# CAN-BUS-UART_v2.net
KiCad netlist of a schematic drawn in EAGLE
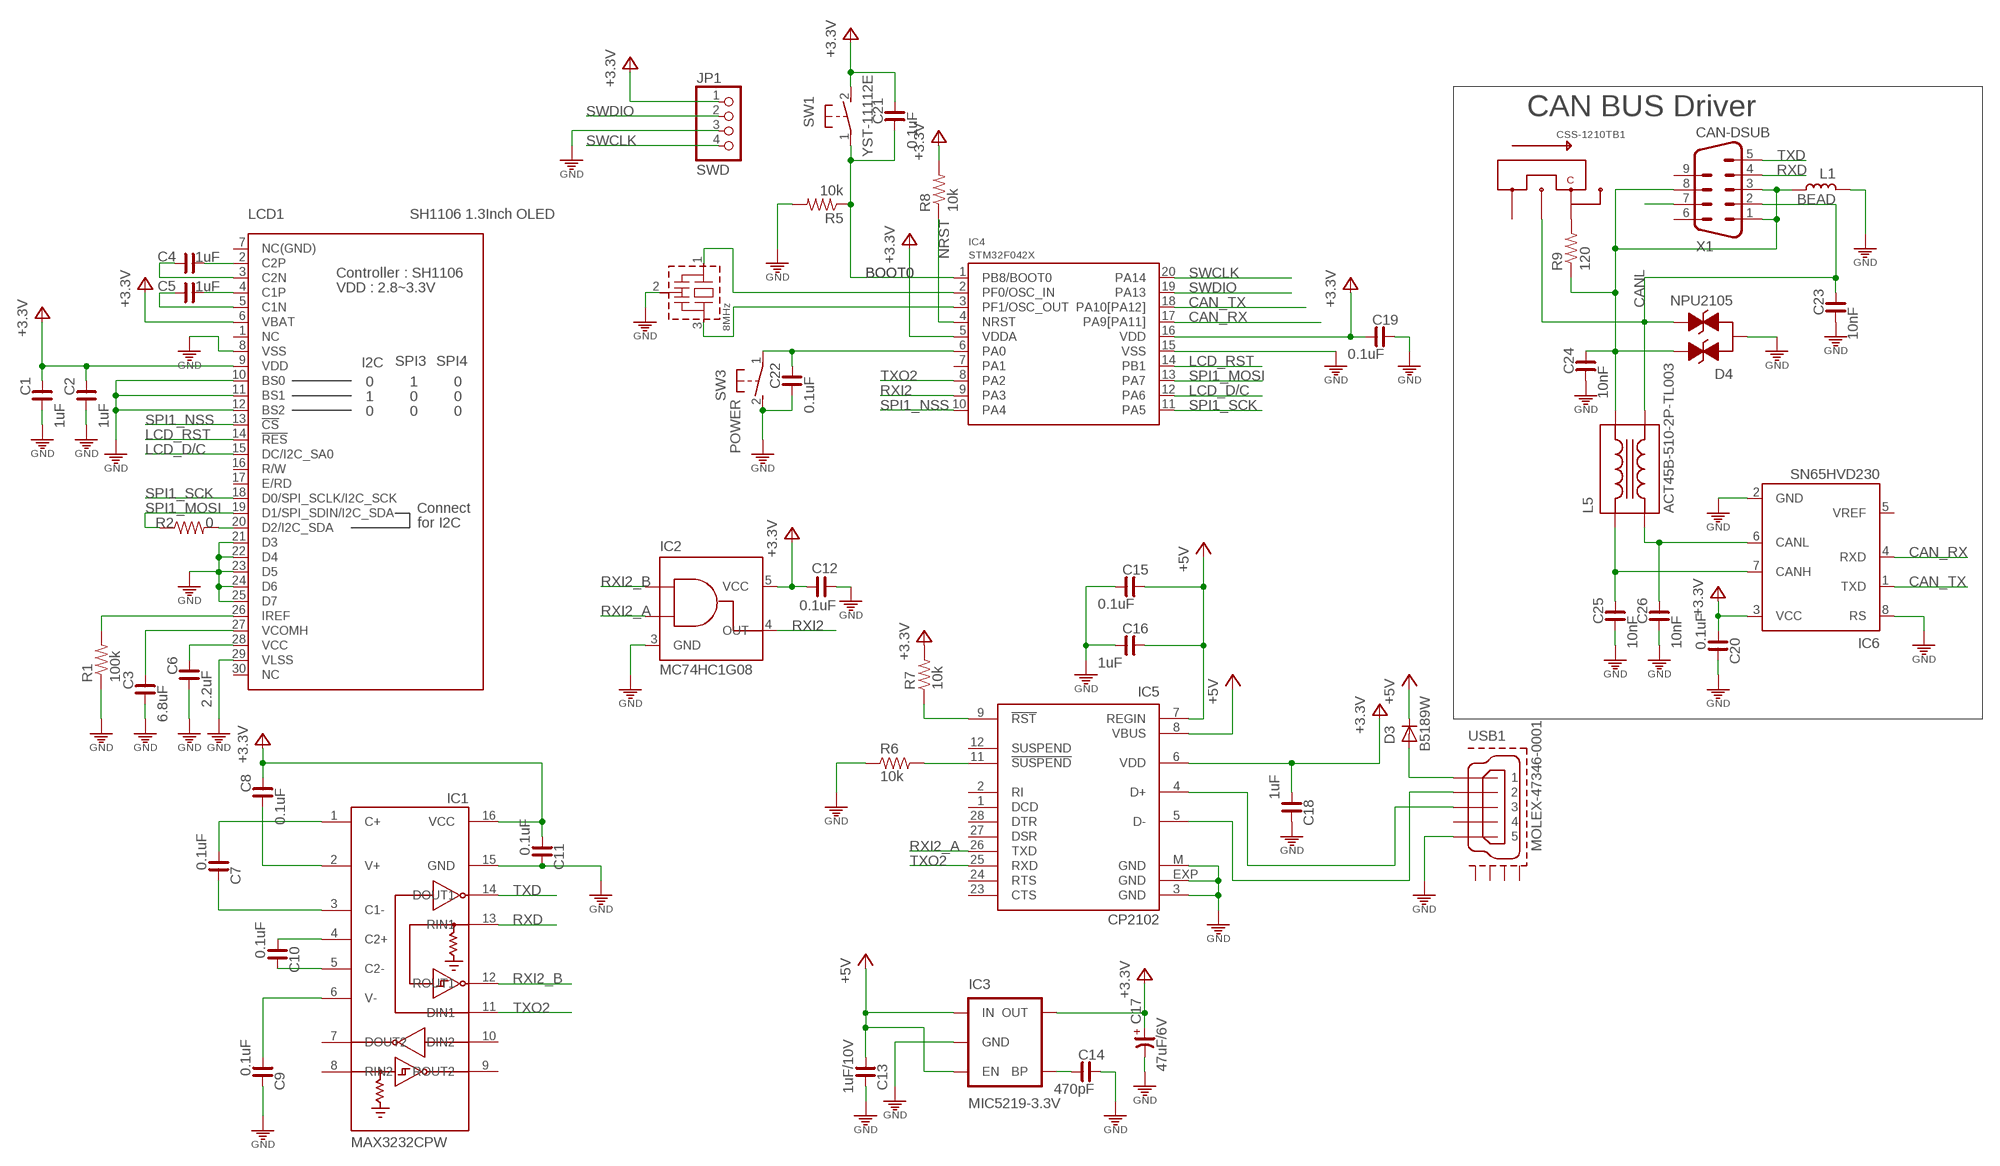
[diagram p0: schematic, sheet 1]

(export (version "E")
  (design (tool "Eeschema 10.0.6"))
  (components
    (comp (ref "C1")
      (value "1uF")
      (footprint "eagle-import:C0603")
      (libsource (lib "eagle-import") (part "C_0603"))
    )
    (comp (ref "C2")
      (value "1uF")
      (footprint "eagle-import:C0603")
      (libsource (lib "eagle-import") (part "C_0603"))
    )
    (comp (ref "C3")
      (value "6.8uF")
      (footprint "eagle-import:C0805")
      (libsource (lib "eagle-import") (part "C_0805"))
    )
    (comp (ref "C4")
      (value "1uF")
      (footprint "eagle-import:C0603")
      (libsource (lib "eagle-import") (part "C_0603"))
    )
    (comp (ref "C5")
      (value "1uF")
      (footprint "eagle-import:C0603")
      (libsource (lib "eagle-import") (part "C_0603"))
    )
    (comp (ref "C6")
      (value "2.2uF")
      (footprint "eagle-import:C0805")
      (libsource (lib "eagle-import") (part "C_0805"))
    )
    (comp (ref "C7")
      (value "0.1uF")
      (footprint "eagle-import:C0603")
      (libsource (lib "eagle-import") (part "C_0603"))
    )
    (comp (ref "C8")
      (value "0.1uF")
      (footprint "eagle-import:C0603")
      (libsource (lib "eagle-import") (part "C_0603"))
    )
    (comp (ref "C9")
      (value "0.1uF")
      (footprint "eagle-import:C0603")
      (libsource (lib "eagle-import") (part "C_0603"))
    )
    (comp (ref "C10")
      (value "0.1uF")
      (footprint "eagle-import:C0603")
      (libsource (lib "eagle-import") (part "C_0603"))
    )
    (comp (ref "C11")
      (value "0.1uF")
      (footprint "eagle-import:C0603")
      (libsource (lib "eagle-import") (part "C_0603"))
    )
    (comp (ref "C12")
      (value "0.1uF")
      (footprint "eagle-import:C0603")
      (libsource (lib "eagle-import") (part "C_0603"))
    )
    (comp (ref "C13")
      (value "1uF/10V")
      (footprint "eagle-import:C0603")
      (libsource (lib "eagle-import") (part "C_0603"))
    )
    (comp (ref "C14")
      (value "470pF")
      (footprint "eagle-import:C0603")
      (libsource (lib "eagle-import") (part "C_0603"))
    )
    (comp (ref "C15")
      (value "0.1uF")
      (footprint "eagle-import:C0603")
      (libsource (lib "eagle-import") (part "C_0603"))
    )
    (comp (ref "C16")
      (value "1uF")
      (footprint "eagle-import:C0603")
      (libsource (lib "eagle-import") (part "C_0603"))
    )
    (comp (ref "C17")
      (value "47uF/6V")
      (footprint "eagle-import:C3528-21_T")
      (libsource (lib "eagle-import") (part "CP_3528-21"))
    )
    (comp (ref "C18")
      (value "1uF")
      (footprint "eagle-import:C0603")
      (libsource (lib "eagle-import") (part "C_0603"))
    )
    (comp (ref "C19")
      (value "0.1uF")
      (footprint "eagle-import:C0603")
      (libsource (lib "eagle-import") (part "C_0603"))
    )
    (comp (ref "C20")
      (value "0.1uF")
      (footprint "eagle-import:C0603")
      (libsource (lib "eagle-import") (part "C_0603"))
    )
    (comp (ref "C21")
      (value "0.1uF")
      (footprint "eagle-import:C0603")
      (libsource (lib "eagle-import") (part "C_0603"))
    )
    (comp (ref "C22")
      (value "0.1uF")
      (footprint "eagle-import:C0603")
      (libsource (lib "eagle-import") (part "C_0603"))
    )
    (comp (ref "C23")
      (value "10nF")
      (footprint "eagle-import:C0603")
      (libsource (lib "eagle-import") (part "C_0603"))
    )
    (comp (ref "C24")
      (value "10nF")
      (footprint "eagle-import:C0603")
      (libsource (lib "eagle-import") (part "C_0603"))
    )
    (comp (ref "C25")
      (value "10nF")
      (footprint "eagle-import:C0603")
      (libsource (lib "eagle-import") (part "C_0603"))
    )
    (comp (ref "C26")
      (value "10nF")
      (footprint "eagle-import:C0603")
      (libsource (lib "eagle-import") (part "C_0603"))
    )
    (comp (ref "D3")
      (value "B5189W")
      (footprint "eagle-import:SOD323")
      (libsource (lib "eagle-import") (part "B5189WN"))
    )
    (comp (ref "D4")
      (value "NPU2105")
      (footprint "eagle-import:SOT23")
      (libsource (lib "eagle-import") (part "NPU2105"))
    )
    (comp (ref "IC1")
      (value "MAX3232CPW")
      (footprint "eagle-import:PW_R-PDSO-G16")
      (libsource (lib "eagle-import") (part "MAX3232MAX232CPW"))
    )
    (comp (ref "IC2")
      (value "MC74HC1G08")
      (footprint "eagle-import:SOT23-5L_MC74HC1G08")
      (libsource (lib "eagle-import") (part "AND_GATE_2INMC74HC1G08"))
    )
    (comp (ref "IC3")
      (value "MIC5219-3.3V")
      (footprint "eagle-import:SOT23-5")
      (libsource (lib "eagle-import") (part "V_REG_LDOSMD"))
    )
    (comp (ref "IC4")
      (value "STM32F042X")
      (footprint "eagle-import:TSSOP20")
      (libsource (lib "eagle-import") (part "STM32F042X"))
    )
    (comp (ref "IC5")
      (value "CP2102")
      (footprint "eagle-import:MLP28")
      (fields (field (name "MF") "FARNELL") (field (name "MPN") "CP2102-GM"))
      (libsource (lib "eagle-import") (part "CP2102"))
    )
    (comp (ref "IC6")
      (value "SN65HVD230")
      (footprint "eagle-import:SO8")
      (libsource (lib "eagle-import") (part "PCA82C250T"))
    )
    (comp (ref "JP1")
      (value "SWD")
      (footprint "eagle-import:1X04M")
      (libsource (lib "eagle-import") (part "PINHD-1X4M"))
    )
    (comp (ref "L1")
      (value "BEAD")
      (footprint "eagle-import:L0805")
      (libsource (lib "eagle-import") (part "L_0805"))
    )
    (comp (ref "L5")
      (value "ACT45B-510-2P-TL003")
      (footprint "eagle-import:ACT45B")
      (libsource (lib "eagle-import") (part "CHOKE_COIL"))
    )
    (comp (ref "LCD1")
      (value "SH1106 1.3Inch OLED")
      (footprint "eagle-import:SH1106_1.3OLED_BUTTOM")
      (libsource (lib "eagle-import") (part "SH1106_1.3_OLEDBUTTOM"))
    )
    (comp (ref "Q1")
      (value "8MHz")
      (footprint "eagle-import:CSTLA_X")
      (libsource (lib "eagle-import") (part "X-TAL-SMALLCSTCE16M00V53"))
    )
    (comp (ref "R1")
      (value "100k")
      (footprint "eagle-import:R0603@1")
      (libsource (lib "eagle-import") (part "R-US_R1608"))
    )
    (comp (ref "R2")
      (value "0")
      (footprint "eagle-import:R0603@1")
      (libsource (lib "eagle-import") (part "R-US_R1608"))
    )
    (comp (ref "R5")
      (value "10k")
      (footprint "eagle-import:R0603@1")
      (libsource (lib "eagle-import") (part "R-US_R1608"))
    )
    (comp (ref "R6")
      (value "10k")
      (footprint "eagle-import:R0603")
      (libsource (lib "eagle-import") (part "R_0603"))
    )
    (comp (ref "R7")
      (value "10k")
      (footprint "eagle-import:R0603")
      (libsource (lib "eagle-import") (part "R_0603"))
    )
    (comp (ref "R8")
      (value "10k")
      (footprint "eagle-import:R0603@1")
      (libsource (lib "eagle-import") (part "R-US_R1608"))
    )
    (comp (ref "R9")
      (value "120")
      (footprint "eagle-import:R0603@1")
      (libsource (lib "eagle-import") (part "R-US_R1608"))
    )
    (comp (ref "SW1")
      (value "YST-11112E")
      (footprint "eagle-import:YST-1112E")
      (libsource (lib "eagle-import") (part "YST-11112E"))
    )
    (comp (ref "SW2")
      (value "CSS-1210TB1")
      (footprint "eagle-import:CSS-1210TB")
      (libsource (lib "eagle-import") (part "CSS-1210TB1"))
    )
    (comp (ref "SW3")
      (value "POWER")
      (footprint "eagle-import:KLT-1105VE")
      (libsource (lib "eagle-import") (part "KLT-1105VE"))
    )
    (comp (ref "USB1")
      (value "MOLEX-47346-0001")
      (footprint "eagle-import:MOLEX-47364-0001")
      (libsource (lib "eagle-import") (part "MOLEX-47346-0001"))
    )
    (comp (ref "X1")
      (value "CAN-DSUB")
      (footprint "eagle-import:M09H-1")
      (libsource (lib "eagle-import") (part "M09KR"))
    )
  )
  (nets
    (net (code "1") (name "+3V3") (class "Default")
      (node (ref "C1") (pin "1") (pinfunction "1_1") (pintype "passive"))
      (node (ref "C11") (pin "2") (pinfunction "2_2") (pintype "passive"))
      (node (ref "C12") (pin "2") (pinfunction "2_2") (pintype "passive"))
      (node (ref "C17") (pin "+") (pinfunction "+_+") (pintype "passive"))
      (node (ref "C18") (pin "2") (pinfunction "2_2") (pintype "passive"))
      (node (ref "C19") (pin "2") (pinfunction "2_2") (pintype "passive"))
      (node (ref "C2") (pin "1") (pinfunction "1_1") (pintype "passive"))
      (node (ref "C20") (pin "2") (pinfunction "2_2") (pintype "passive"))
      (node (ref "C21") (pin "1") (pinfunction "1_1") (pintype "passive"))
      (node (ref "C8") (pin "1") (pinfunction "1_1") (pintype "passive"))
      (node (ref "IC1") (pin "16") (pinfunction "VCC_16") (pintype "power_in"))
      (node (ref "IC2") (pin "5") (pinfunction "VCC_5") (pintype "passive"))
      (node (ref "IC3") (pin "5") (pinfunction "OUT_5") (pintype "passive"))
      (node (ref "IC4") (pin "16") (pinfunction "VDD_16") (pintype "power_in"))
      (node (ref "IC4") (pin "5") (pinfunction "VDDA_5") (pintype "power_in"))
      (node (ref "IC5") (pin "6") (pinfunction "VDD_6") (pintype "power_in"))
      (node (ref "IC6") (pin "3") (pinfunction "VCC_3") (pintype "power_in"))
      (node (ref "JP1") (pin "1") (pinfunction "1_1") (pintype "passive"))
      (node (ref "LCD1") (pin "6") (pinfunction "VBAT_6") (pintype "passive"))
      (node (ref "LCD1") (pin "9") (pinfunction "VDD_9") (pintype "passive"))
      (node (ref "R7") (pin "2") (pinfunction "2_2") (pintype "passive"))
      (node (ref "R8") (pin "2") (pinfunction "2_2") (pintype "passive"))
      (node (ref "SW1") (pin "2") (pinfunction "2_2") (pintype "passive"))
    )
    (net (code "2") (name "+5V") (class "Default")
      (node (ref "C13") (pin "2") (pinfunction "2_2") (pintype "passive"))
      (node (ref "C15") (pin "1") (pinfunction "1_1") (pintype "passive"))
      (node (ref "C16") (pin "1") (pinfunction "1_1") (pintype "passive"))
      (node (ref "D3") (pin "C") (pinfunction "C_C") (pintype "passive"))
      (node (ref "IC3") (pin "1") (pinfunction "IN_1") (pintype "input"))
      (node (ref "IC3") (pin "3") (pinfunction "EN_3") (pintype "input"))
      (node (ref "IC5") (pin "7") (pinfunction "REGIN_7") (pintype "passive"))
      (node (ref "IC5") (pin "8") (pinfunction "VBUS_8") (pintype "input"))
    )
    (net (code "3") (name "/BOOT0") (class "Default")
      (node (ref "C21") (pin "2") (pinfunction "2_2") (pintype "passive"))
      (node (ref "IC4") (pin "1") (pinfunction "PB8/BOOT0_1") (pintype "bidirectional"))
      (node (ref "R5") (pin "1") (pinfunction "1_1") (pintype "passive"))
      (node (ref "SW1") (pin "1") (pinfunction "1_1") (pintype "passive"))
    )
    (net (code "4") (name "/CANL") (class "Default")
      (node (ref "C23") (pin "1") (pinfunction "1_1") (pintype "passive"))
      (node (ref "D4") (pin "S") (pinfunction "PIN2_S") (pintype "passive"))
      (node (ref "L5") (pin "3") (pinfunction "3_3") (pintype "passive"))
      (node (ref "SW2") (pin "2") (pinfunction "2_2") (pintype "bidirectional"))
      (node (ref "X1") (pin "2") (pinfunction "2_2") (pintype "passive"))
    )
    (net (code "5") (name "/CAN_RX") (class "Default")
      (node (ref "IC4") (pin "17") (pinfunction "PA9[PA11]_17") (pintype "bidirectional"))
      (node (ref "IC6") (pin "4") (pinfunction "RXD_4") (pintype "output"))
    )
    (net (code "6") (name "/CAN_TX") (class "Default")
      (node (ref "IC4") (pin "18") (pinfunction "PA10[PA12]_18") (pintype "bidirectional"))
      (node (ref "IC6") (pin "1") (pinfunction "TXD_1") (pintype "input"))
    )
    (net (code "7") (name "/LCD_D{slash}C") (class "Default")
      (node (ref "IC4") (pin "12") (pinfunction "PA6_12") (pintype "bidirectional"))
      (node (ref "LCD1") (pin "15") (pinfunction "DC/I2C_SA0_15") (pintype "passive"))
    )
    (net (code "8") (name "/LCD_RST") (class "Default")
      (node (ref "IC4") (pin "14") (pinfunction "PB1_14") (pintype "bidirectional"))
      (node (ref "LCD1") (pin "14") (pinfunction "~{RES}_14") (pintype "passive"))
    )
    (net (code "9") (name "/NRST") (class "Default")
      (node (ref "IC4") (pin "4") (pinfunction "NRST_4") (pintype "bidirectional"))
      (node (ref "R8") (pin "1") (pinfunction "1_1") (pintype "passive"))
    )
    (net (code "10") (name "/RXD") (class "Default")
      (node (ref "IC1") (pin "13") (pinfunction "RIN1_13") (pintype "input"))
      (node (ref "X1") (pin "4") (pinfunction "4_4") (pintype "passive"))
    )
    (net (code "11") (name "/RXI2") (class "Default")
      (node (ref "IC2") (pin "4") (pinfunction "OUT_4") (pintype "output"))
      (node (ref "IC4") (pin "9") (pinfunction "PA3_9") (pintype "bidirectional"))
    )
    (net (code "12") (name "/RXI2_A") (class "Default")
      (node (ref "IC2") (pin "2") (pinfunction "INA_2") (pintype "input"))
      (node (ref "IC5") (pin "26") (pinfunction "TXD_26") (pintype "output"))
    )
    (net (code "13") (name "/RXI2_B") (class "Default")
      (node (ref "IC1") (pin "12") (pinfunction "ROUT1_12") (pintype "input"))
      (node (ref "IC2") (pin "1") (pinfunction "INB_1") (pintype "input"))
    )
    (net (code "14") (name "/SPI1_MOSI") (class "Default")
      (node (ref "IC4") (pin "13") (pinfunction "PA7_13") (pintype "bidirectional"))
      (node (ref "LCD1") (pin "19") (pinfunction "D1/SPI_SDIN/I2C_SDA_19") (pintype "passive"))
      (node (ref "R2") (pin "1") (pinfunction "1_1") (pintype "passive"))
    )
    (net (code "15") (name "/SPI1_NSS") (class "Default")
      (node (ref "IC4") (pin "10") (pinfunction "PA4_10") (pintype "bidirectional"))
      (node (ref "LCD1") (pin "13") (pinfunction "~{CS}_13") (pintype "passive"))
    )
    (net (code "16") (name "/SPI1_SCK") (class "Default")
      (node (ref "IC4") (pin "11") (pinfunction "PA5_11") (pintype "bidirectional"))
      (node (ref "LCD1") (pin "18") (pinfunction "D0/SPI_SCLK/I2C_SCK_18") (pintype "passive"))
    )
    (net (code "17") (name "/SWCLK") (class "Default")
      (node (ref "IC4") (pin "20") (pinfunction "PA14_20") (pintype "bidirectional"))
      (node (ref "JP1") (pin "4") (pinfunction "4_4") (pintype "passive"))
    )
    (net (code "18") (name "/SWDIO") (class "Default")
      (node (ref "IC4") (pin "19") (pinfunction "PA13_19") (pintype "bidirectional"))
      (node (ref "JP1") (pin "2") (pinfunction "2_2") (pintype "passive"))
    )
    (net (code "19") (name "/TXD") (class "Default")
      (node (ref "IC1") (pin "14") (pinfunction "DOUT1_14") (pintype "output"))
      (node (ref "X1") (pin "5") (pinfunction "5_5") (pintype "passive"))
    )
    (net (code "20") (name "/TXO2") (class "Default")
      (node (ref "IC1") (pin "11") (pinfunction "DIN1_11") (pintype "input"))
      (node (ref "IC4") (pin "8") (pinfunction "PA2_8") (pintype "bidirectional"))
      (node (ref "IC5") (pin "25") (pinfunction "RXD_25") (pintype "input"))
    )
    (net (code "21") (name "GND") (class "Default")
      (node (ref "C1") (pin "2") (pinfunction "2_2") (pintype "passive"))
      (node (ref "C11") (pin "1") (pinfunction "1_1") (pintype "passive"))
      (node (ref "C12") (pin "1") (pinfunction "1_1") (pintype "passive"))
      (node (ref "C13") (pin "1") (pinfunction "1_1") (pintype "passive"))
      (node (ref "C14") (pin "1") (pinfunction "1_1") (pintype "passive"))
      (node (ref "C15") (pin "2") (pinfunction "2_2") (pintype "passive"))
      (node (ref "C16") (pin "2") (pinfunction "2_2") (pintype "passive"))
      (node (ref "C17") (pin "-") (pinfunction "-_-") (pintype "passive"))
      (node (ref "C18") (pin "1") (pinfunction "1_1") (pintype "passive"))
      (node (ref "C19") (pin "1") (pinfunction "1_1") (pintype "passive"))
      (node (ref "C2") (pin "2") (pinfunction "2_2") (pintype "passive"))
      (node (ref "C20") (pin "1") (pinfunction "1_1") (pintype "passive"))
      (node (ref "C22") (pin "2") (pinfunction "2_2") (pintype "passive"))
      (node (ref "C23") (pin "2") (pinfunction "2_2") (pintype "passive"))
      (node (ref "C24") (pin "2") (pinfunction "2_2") (pintype "passive"))
      (node (ref "C25") (pin "2") (pinfunction "2_2") (pintype "passive"))
      (node (ref "C26") (pin "2") (pinfunction "2_2") (pintype "passive"))
      (node (ref "C3") (pin "2") (pinfunction "2_2") (pintype "passive"))
      (node (ref "C6") (pin "2") (pinfunction "2_2") (pintype "passive"))
      (node (ref "C9") (pin "1") (pinfunction "1_1") (pintype "passive"))
      (node (ref "D4") (pin "D") (pinfunction "PIN3_D") (pintype "passive"))
      (node (ref "IC1") (pin "15") (pinfunction "GND_15") (pintype "power_in"))
      (node (ref "IC2") (pin "3") (pinfunction "GND_3") (pintype "passive"))
      (node (ref "IC3") (pin "2") (pinfunction "GND_2") (pintype "input"))
      (node (ref "IC4") (pin "15") (pinfunction "VSS_15") (pintype "power_in"))
      (node (ref "IC5") (pin "3") (pinfunction "GND_3") (pintype "power_in"))
      (node (ref "IC5") (pin "EXP") (pinfunction "GND_EXP") (pintype "power_in"))
      (node (ref "IC5") (pin "M") (pinfunction "GND_M") (pintype "power_in"))
      (node (ref "IC6") (pin "2") (pinfunction "GND_2") (pintype "power_in"))
      (node (ref "IC6") (pin "8") (pinfunction "RS_8") (pintype "input"))
      (node (ref "JP1") (pin "3") (pinfunction "3_3") (pintype "passive"))
      (node (ref "L1") (pin "2") (pinfunction "2_2") (pintype "passive"))
      (node (ref "LCD1") (pin "10") (pinfunction "BS0_10") (pintype "passive"))
      (node (ref "LCD1") (pin "11") (pinfunction "BS1_11") (pintype "passive"))
      (node (ref "LCD1") (pin "12") (pinfunction "BS2_12") (pintype "passive"))
      (node (ref "LCD1") (pin "21") (pinfunction "D3_21") (pintype "passive"))
      (node (ref "LCD1") (pin "22") (pinfunction "D4_22") (pintype "passive"))
      (node (ref "LCD1") (pin "23") (pinfunction "D5_23") (pintype "passive"))
      (node (ref "LCD1") (pin "24") (pinfunction "D6_24") (pintype "passive"))
      (node (ref "LCD1") (pin "25") (pinfunction "D7_25") (pintype "passive"))
      (node (ref "LCD1") (pin "29") (pinfunction "VLSS_29") (pintype "passive"))
      (node (ref "LCD1") (pin "8") (pinfunction "VSS_8") (pintype "passive"))
      (node (ref "Q1") (pin "2") (pinfunction "GND_2") (pintype "power_in"))
      (node (ref "R1") (pin "1") (pinfunction "1_1") (pintype "passive"))
      (node (ref "R5") (pin "2") (pinfunction "2_2") (pintype "passive"))
      (node (ref "R6") (pin "1") (pinfunction "1_1") (pintype "passive"))
      (node (ref "SW3") (pin "2") (pinfunction "2_2") (pintype "passive"))
      (node (ref "USB1") (pin "5") (pinfunction "5_5") (pintype "input"))
    )
    (net (code "22") (name "Net-(D3-PadA)") (class "Default")
      (node (ref "D3") (pin "A") (pinfunction "A_A") (pintype "passive"))
      (node (ref "USB1") (pin "1") (pinfunction "1_1") (pintype "input"))
    )
    (net (code "23") (name "Net-(D4-PIN1)") (class "Default")
      (node (ref "C24") (pin "1") (pinfunction "1_1") (pintype "passive"))
      (node (ref "D4") (pin "G") (pinfunction "PIN1_G") (pintype "passive"))
      (node (ref "L1") (pin "1") (pinfunction "1_1") (pintype "passive"))
      (node (ref "L5") (pin "4") (pinfunction "4_4") (pintype "passive"))
      (node (ref "R9") (pin "1") (pinfunction "1_1") (pintype "passive"))
      (node (ref "X1") (pin "1") (pinfunction "1_1") (pintype "passive"))
      (node (ref "X1") (pin "3") (pinfunction "3_3") (pintype "passive"))
      (node (ref "X1") (pin "8") (pinfunction "8_8") (pintype "passive"))
    )
    (net (code "24") (name "Net-(IC1-C+)") (class "Default")
      (node (ref "C7") (pin "2") (pinfunction "2_2") (pintype "passive"))
      (node (ref "IC1") (pin "1") (pinfunction "C+_1") (pintype "passive"))
    )
    (net (code "25") (name "Net-(IC1-C1-)") (class "Default")
      (node (ref "C7") (pin "1") (pinfunction "1_1") (pintype "passive"))
      (node (ref "IC1") (pin "3") (pinfunction "C1-_3") (pintype "power_in"))
    )
    (net (code "26") (name "Net-(IC1-C2+)") (class "Default")
      (node (ref "C10") (pin "2") (pinfunction "2_2") (pintype "passive"))
      (node (ref "IC1") (pin "4") (pinfunction "C2+_4") (pintype "passive"))
    )
    (net (code "27") (name "Net-(IC1-C2-)") (class "Default")
      (node (ref "C10") (pin "1") (pinfunction "1_1") (pintype "passive"))
      (node (ref "IC1") (pin "5") (pinfunction "C2-_5") (pintype "passive"))
    )
    (net (code "28") (name "Net-(IC1-V+)") (class "Default")
      (node (ref "C8") (pin "2") (pinfunction "2_2") (pintype "passive"))
      (node (ref "IC1") (pin "2") (pinfunction "V+_2") (pintype "passive"))
    )
    (net (code "29") (name "Net-(IC1-V-)") (class "Default")
      (node (ref "C9") (pin "2") (pinfunction "2_2") (pintype "passive"))
      (node (ref "IC1") (pin "6") (pinfunction "V-_6") (pintype "passive"))
    )
    (net (code "30") (name "Net-(IC3-BP)") (class "Default")
      (node (ref "C14") (pin "2") (pinfunction "2_2") (pintype "passive"))
      (node (ref "IC3") (pin "4") (pinfunction "BP_4") (pintype "input"))
    )
    (net (code "31") (name "Net-(IC4-PA0)") (class "Default")
      (node (ref "C22") (pin "1") (pinfunction "1_1") (pintype "passive"))
      (node (ref "IC4") (pin "6") (pinfunction "PA0_6") (pintype "bidirectional"))
      (node (ref "SW3") (pin "1") (pinfunction "1_1") (pintype "passive"))
    )
    (net (code "32") (name "Net-(IC4-PF0{slash}OSC_IN)") (class "Default")
      (node (ref "IC4") (pin "2") (pinfunction "PF0/OSC_IN_2") (pintype "bidirectional"))
      (node (ref "Q1") (pin "1") (pinfunction "IN_1") (pintype "output"))
    )
    (net (code "33") (name "Net-(IC4-PF1{slash}OSC_OUT)") (class "Default")
      (node (ref "IC4") (pin "3") (pinfunction "PF1/OSC_OUT_3") (pintype "bidirectional"))
      (node (ref "Q1") (pin "3") (pinfunction "OUT_3") (pintype "input"))
    )
    (net (code "34") (name "Net-(IC5-D+)") (class "Default")
      (node (ref "IC5") (pin "4") (pinfunction "D+_4") (pintype "bidirectional"))
      (node (ref "USB1") (pin "3") (pinfunction "3_3") (pintype "input"))
    )
    (net (code "35") (name "Net-(IC5-D-)") (class "Default")
      (node (ref "IC5") (pin "5") (pinfunction "D-_5") (pintype "bidirectional"))
      (node (ref "USB1") (pin "2") (pinfunction "2_2") (pintype "input"))
    )
    (net (code "36") (name "Net-(IC5-~{RST})") (class "Default")
      (node (ref "IC5") (pin "9") (pinfunction "~{RST}_9") (pintype "bidirectional"))
      (node (ref "R7") (pin "1") (pinfunction "1_1") (pintype "passive"))
    )
    (net (code "37") (name "Net-(IC5-~{SUSPEND})") (class "Default")
      (node (ref "IC5") (pin "11") (pinfunction "~{SUSPEND}_11") (pintype "output"))
      (node (ref "R6") (pin "2") (pinfunction "2_2") (pintype "passive"))
    )
    (net (code "38") (name "Net-(IC6-CANH)") (class "Default")
      (node (ref "C25") (pin "1") (pinfunction "1_1") (pintype "passive"))
      (node (ref "IC6") (pin "7") (pinfunction "CANH_7") (pintype "bidirectional"))
      (node (ref "L5") (pin "1") (pinfunction "1_1") (pintype "passive"))
    )
    (net (code "39") (name "Net-(IC6-CANL)") (class "Default")
      (node (ref "C26") (pin "1") (pinfunction "1_1") (pintype "passive"))
      (node (ref "IC6") (pin "6") (pinfunction "CANL_6") (pintype "bidirectional"))
      (node (ref "L5") (pin "2") (pinfunction "2_2") (pintype "passive"))
    )
    (net (code "40") (name "Net-(LCD1-C1N)") (class "Default")
      (node (ref "C5") (pin "1") (pinfunction "1_1") (pintype "passive"))
      (node (ref "LCD1") (pin "5") (pinfunction "C1N_5") (pintype "passive"))
    )
    (net (code "41") (name "Net-(LCD1-C1P)") (class "Default")
      (node (ref "C5") (pin "2") (pinfunction "2_2") (pintype "passive"))
      (node (ref "LCD1") (pin "4") (pinfunction "C1P_4") (pintype "passive"))
    )
    (net (code "42") (name "Net-(LCD1-C2N)") (class "Default")
      (node (ref "C4") (pin "1") (pinfunction "1_1") (pintype "passive"))
      (node (ref "LCD1") (pin "3") (pinfunction "C2N_3") (pintype "passive"))
    )
    (net (code "43") (name "Net-(LCD1-C2P)") (class "Default")
      (node (ref "C4") (pin "2") (pinfunction "2_2") (pintype "passive"))
      (node (ref "LCD1") (pin "2") (pinfunction "C2P_2") (pintype "passive"))
    )
    (net (code "44") (name "Net-(LCD1-D2{slash}I2C_SDA)") (class "Default")
      (node (ref "LCD1") (pin "20") (pinfunction "D2/I2C_SDA_20") (pintype "passive"))
      (node (ref "R2") (pin "2") (pinfunction "2_2") (pintype "passive"))
    )
    (net (code "45") (name "Net-(LCD1-IREF)") (class "Default")
      (node (ref "LCD1") (pin "26") (pinfunction "IREF_26") (pintype "passive"))
      (node (ref "R1") (pin "2") (pinfunction "2_2") (pintype "passive"))
    )
    (net (code "46") (name "Net-(LCD1-VCC)") (class "Default")
      (node (ref "C6") (pin "1") (pinfunction "1_1") (pintype "passive"))
      (node (ref "LCD1") (pin "28") (pinfunction "VCC_28") (pintype "passive"))
    )
    (net (code "47") (name "Net-(LCD1-VCOMH)") (class "Default")
      (node (ref "C3") (pin "1") (pinfunction "1_1") (pintype "passive"))
      (node (ref "LCD1") (pin "27") (pinfunction "VCOMH_27") (pintype "passive"))
    )
    (net (code "48") (name "Net-(R9-Pad2)") (class "Default")
      (node (ref "R9") (pin "2") (pinfunction "2_2") (pintype "passive"))
      (node (ref "SW2") (pin "3") (pinfunction "3_3") (pintype "bidirectional"))
    )
    (net (code "49") (name "unconnected-(IC1-DIN2-Pad10)") (class "Default")
      (node (ref "IC1") (pin "10") (pinfunction "DIN2_10") (pintype "input"))
    )
    (net (code "50") (name "unconnected-(IC1-DOUT2-Pad7)") (class "Default")
      (node (ref "IC1") (pin "7") (pinfunction "DOUT2_7") (pintype "output"))
    )
    (net (code "51") (name "unconnected-(IC1-RIN2-Pad8)") (class "Default")
      (node (ref "IC1") (pin "8") (pinfunction "RIN2_8") (pintype "input"))
    )
    (net (code "52") (name "unconnected-(IC1-ROUT2-Pad9)") (class "Default")
      (node (ref "IC1") (pin "9") (pinfunction "ROUT2_9") (pintype "output"))
    )
    (net (code "53") (name "unconnected-(IC4-PA1-Pad7)") (class "Default")
      (node (ref "IC4") (pin "7") (pinfunction "PA1_7") (pintype "bidirectional"))
    )
    (net (code "54") (name "unconnected-(IC5-CTS-Pad23)") (class "Default")
      (node (ref "IC5") (pin "23") (pinfunction "CTS_23") (pintype "input"))
    )
    (net (code "55") (name "unconnected-(IC5-DCD-Pad1)") (class "Default")
      (node (ref "IC5") (pin "1") (pinfunction "DCD_1") (pintype "input"))
    )
    (net (code "56") (name "unconnected-(IC5-DSR-Pad27)") (class "Default")
      (node (ref "IC5") (pin "27") (pinfunction "DSR_27") (pintype "input"))
    )
    (net (code "57") (name "unconnected-(IC5-DTR-Pad28)") (class "Default")
      (node (ref "IC5") (pin "28") (pinfunction "DTR_28") (pintype "output"))
    )
    (net (code "58") (name "unconnected-(IC5-RI-Pad2)") (class "Default")
      (node (ref "IC5") (pin "2") (pinfunction "RI_2") (pintype "input"))
    )
    (net (code "59") (name "unconnected-(IC5-RTS-Pad24)") (class "Default")
      (node (ref "IC5") (pin "24") (pinfunction "RTS_24") (pintype "output"))
    )
    (net (code "60") (name "unconnected-(IC5-SUSPEND-Pad12)") (class "Default")
      (node (ref "IC5") (pin "12") (pinfunction "SUSPEND_12") (pintype "output"))
    )
    (net (code "61") (name "unconnected-(IC6-VREF-Pad5)") (class "Default")
      (node (ref "IC6") (pin "5") (pinfunction "VREF_5") (pintype "output"))
    )
    (net (code "62") (name "unconnected-(LCD1-E{slash}RD-Pad17)") (class "Default")
      (node (ref "LCD1") (pin "17") (pinfunction "E/RD_17") (pintype "passive"))
    )
    (net (code "63") (name "unconnected-(LCD1-NC(GND)-Pad7)") (class "Default")
      (node (ref "LCD1") (pin "7") (pinfunction "NC(GND)_7") (pintype "passive"))
    )
    (net (code "64") (name "unconnected-(LCD1-NC-Pad1)") (class "Default")
      (node (ref "LCD1") (pin "1") (pinfunction "NC_1") (pintype "no_connect"))
    )
    (net (code "65") (name "unconnected-(LCD1-NC-Pad30)") (class "Default")
      (node (ref "LCD1") (pin "30") (pinfunction "NC_30") (pintype "passive"))
    )
    (net (code "66") (name "unconnected-(LCD1-R{slash}W-Pad16)") (class "Default")
      (node (ref "LCD1") (pin "16") (pinfunction "R/W_16") (pintype "passive"))
    )
    (net (code "67") (name "unconnected-(SW2-Pad1)") (class "Default")
      (node (ref "SW2") (pin "1") (pinfunction "1_1") (pintype "bidirectional"))
    )
    (net (code "68") (name "unconnected-(USB1-Pad4)") (class "Default")
      (node (ref "USB1") (pin "4") (pinfunction "4_4") (pintype "input"))
    )
    (net (code "69") (name "unconnected-(USB1-PadGND1)") (class "Default")
      (node (ref "USB1") (pin "GND1") (pinfunction "GND1_GND1") (pintype "bidirectional"))
    )
    (net (code "70") (name "unconnected-(USB1-PadGND2)") (class "Default")
      (node (ref "USB1") (pin "GND2") (pinfunction "GND2_GND2") (pintype "bidirectional"))
    )
    (net (code "71") (name "unconnected-(USB1-PadGND3)") (class "Default")
      (node (ref "USB1") (pin "GND3") (pinfunction "GND3_GND3") (pintype "bidirectional"))
    )
    (net (code "72") (name "unconnected-(USB1-PadGND4)") (class "Default")
      (node (ref "USB1") (pin "GND4") (pinfunction "GND4_GND4") (pintype "bidirectional"))
    )
    (net (code "73") (name "unconnected-(X1-Pad6)") (class "Default")
      (node (ref "X1") (pin "6") (pinfunction "6_6") (pintype "passive"))
    )
    (net (code "74") (name "unconnected-(X1-Pad7)") (class "Default")
      (node (ref "X1") (pin "7") (pinfunction "7_7") (pintype "passive"))
    )
    (net (code "75") (name "unconnected-(X1-Pad9)") (class "Default")
      (node (ref "X1") (pin "9") (pinfunction "9_9") (pintype "passive"))
    )
  )
)
